# Mikrobus-Proto-18.net
KiCad netlist of a schematic drawn in EAGLE
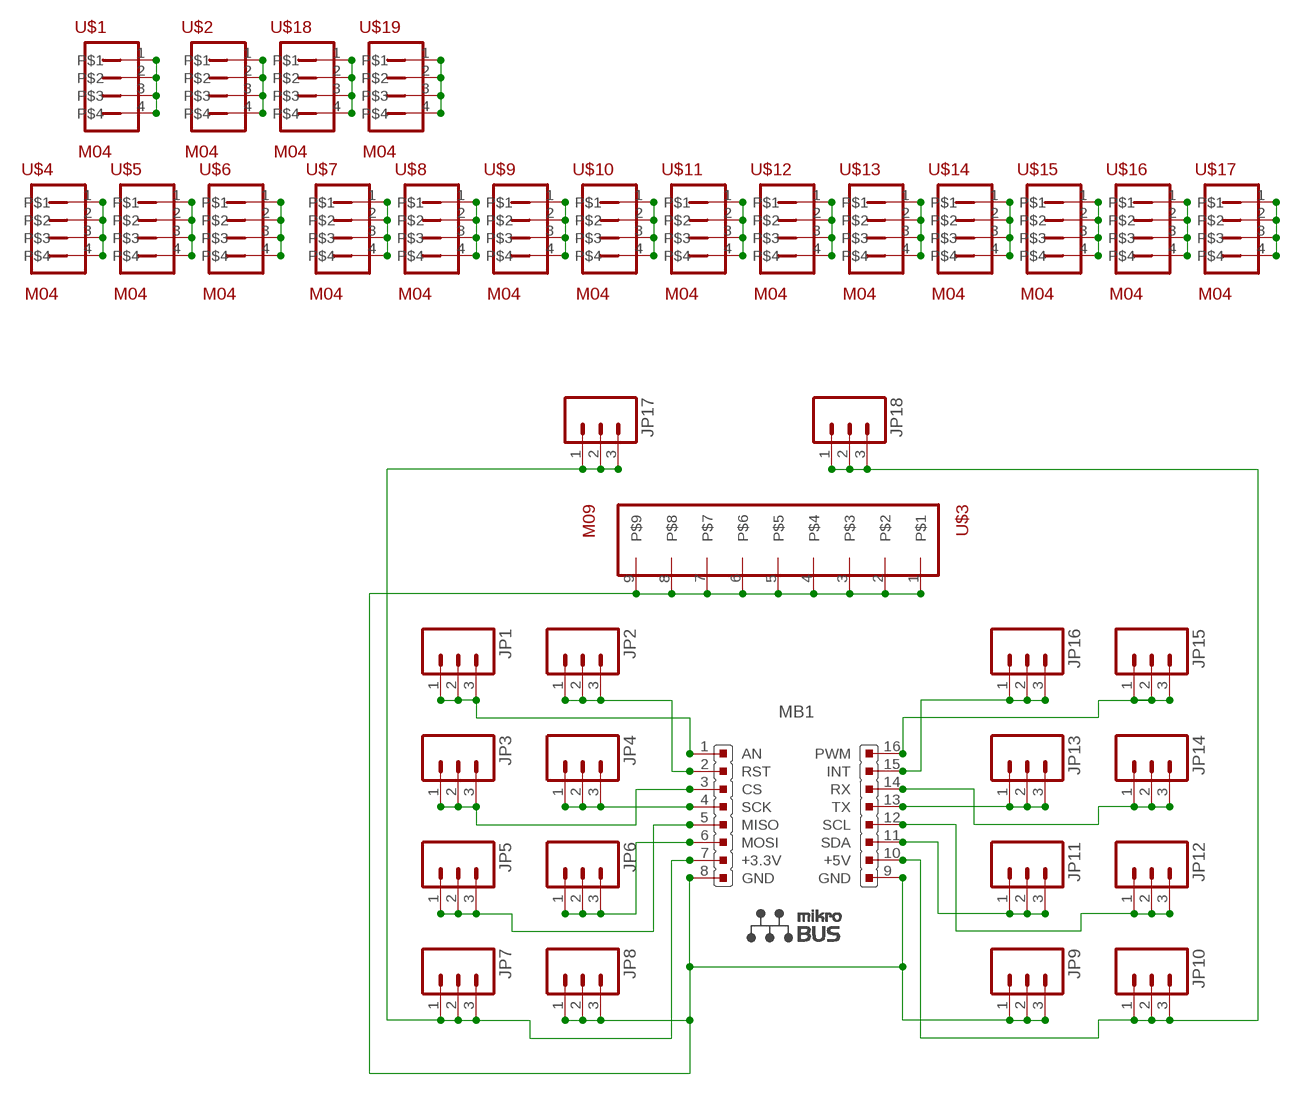
[diagram p0: schematic, sheet 1]

(export (version "E")
  (design (tool "Eeschema 10.0.6"))
  (components
    (comp (ref "JP1")
      (value "M03PTH")
      (footprint "eagle-import:1X03")
      (libsource (lib "eagle-import") (part "M03PTH"))
    )
    (comp (ref "JP2")
      (value "M03PTH")
      (footprint "eagle-import:1X03")
      (libsource (lib "eagle-import") (part "M03PTH"))
    )
    (comp (ref "JP3")
      (value "M03PTH")
      (footprint "eagle-import:1X03")
      (libsource (lib "eagle-import") (part "M03PTH"))
    )
    (comp (ref "JP4")
      (value "M03PTH")
      (footprint "eagle-import:1X03")
      (libsource (lib "eagle-import") (part "M03PTH"))
    )
    (comp (ref "JP5")
      (value "M03PTH")
      (footprint "eagle-import:1X03")
      (libsource (lib "eagle-import") (part "M03PTH"))
    )
    (comp (ref "JP6")
      (value "M03PTH")
      (footprint "eagle-import:1X03")
      (libsource (lib "eagle-import") (part "M03PTH"))
    )
    (comp (ref "JP7")
      (value "M03PTH")
      (footprint "eagle-import:1X03")
      (libsource (lib "eagle-import") (part "M03PTH"))
    )
    (comp (ref "JP8")
      (value "M03PTH")
      (footprint "eagle-import:1X03")
      (libsource (lib "eagle-import") (part "M03PTH"))
    )
    (comp (ref "JP9")
      (value "M03PTH")
      (footprint "eagle-import:1X03")
      (libsource (lib "eagle-import") (part "M03PTH"))
    )
    (comp (ref "JP10")
      (value "M03PTH")
      (footprint "eagle-import:1X03")
      (libsource (lib "eagle-import") (part "M03PTH"))
    )
    (comp (ref "JP11")
      (value "M03PTH")
      (footprint "eagle-import:1X03")
      (libsource (lib "eagle-import") (part "M03PTH"))
    )
    (comp (ref "JP12")
      (value "M03PTH")
      (footprint "eagle-import:1X03")
      (libsource (lib "eagle-import") (part "M03PTH"))
    )
    (comp (ref "JP13")
      (value "M03PTH")
      (footprint "eagle-import:1X03")
      (libsource (lib "eagle-import") (part "M03PTH"))
    )
    (comp (ref "JP14")
      (value "M03PTH")
      (footprint "eagle-import:1X03")
      (libsource (lib "eagle-import") (part "M03PTH"))
    )
    (comp (ref "JP15")
      (value "M03PTH")
      (footprint "eagle-import:1X03")
      (libsource (lib "eagle-import") (part "M03PTH"))
    )
    (comp (ref "JP16")
      (value "M03PTH")
      (footprint "eagle-import:1X03")
      (libsource (lib "eagle-import") (part "M03PTH"))
    )
    (comp (ref "JP17")
      (value "M03PTH")
      (footprint "eagle-import:1X03")
      (libsource (lib "eagle-import") (part "M03PTH"))
    )
    (comp (ref "JP18")
      (value "M03PTH")
      (footprint "eagle-import:1X03")
      (libsource (lib "eagle-import") (part "M03PTH"))
    )
    (comp (ref "MB1")
      (value "MIKROBUS")
      (footprint "eagle-import:MIKROBUS")
      (libsource (lib "eagle-import") (part "MIKROBUS"))
    )
    (comp (ref "U$1")
      (value "M04")
      (footprint "eagle-import:1X04")
      (libsource (lib "eagle-import") (part "M04"))
    )
    (comp (ref "U$2")
      (value "M04")
      (footprint "eagle-import:1X04")
      (libsource (lib "eagle-import") (part "M04"))
    )
    (comp (ref "U$3")
      (value "M09")
      (footprint "eagle-import:1X09")
      (libsource (lib "eagle-import") (part "M09"))
    )
    (comp (ref "U$4")
      (value "M04")
      (footprint "eagle-import:1X04")
      (libsource (lib "eagle-import") (part "M04"))
    )
    (comp (ref "U$5")
      (value "M04")
      (footprint "eagle-import:1X04")
      (libsource (lib "eagle-import") (part "M04"))
    )
    (comp (ref "U$6")
      (value "M04")
      (footprint "eagle-import:1X04")
      (libsource (lib "eagle-import") (part "M04"))
    )
    (comp (ref "U$7")
      (value "M04")
      (footprint "eagle-import:1X04")
      (libsource (lib "eagle-import") (part "M04"))
    )
    (comp (ref "U$8")
      (value "M04")
      (footprint "eagle-import:1X04")
      (libsource (lib "eagle-import") (part "M04"))
    )
    (comp (ref "U$9")
      (value "M04")
      (footprint "eagle-import:1X04")
      (libsource (lib "eagle-import") (part "M04"))
    )
    (comp (ref "U$10")
      (value "M04")
      (footprint "eagle-import:1X04")
      (libsource (lib "eagle-import") (part "M04"))
    )
    (comp (ref "U$11")
      (value "M04")
      (footprint "eagle-import:1X04")
      (libsource (lib "eagle-import") (part "M04"))
    )
    (comp (ref "U$12")
      (value "M04")
      (footprint "eagle-import:1X04")
      (libsource (lib "eagle-import") (part "M04"))
    )
    (comp (ref "U$13")
      (value "M04")
      (footprint "eagle-import:1X04")
      (libsource (lib "eagle-import") (part "M04"))
    )
    (comp (ref "U$14")
      (value "M04")
      (footprint "eagle-import:1X04")
      (libsource (lib "eagle-import") (part "M04"))
    )
    (comp (ref "U$15")
      (value "M04")
      (footprint "eagle-import:1X04")
      (libsource (lib "eagle-import") (part "M04"))
    )
    (comp (ref "U$16")
      (value "M04")
      (footprint "eagle-import:1X04")
      (libsource (lib "eagle-import") (part "M04"))
    )
    (comp (ref "U$17")
      (value "M04")
      (footprint "eagle-import:1X04")
      (libsource (lib "eagle-import") (part "M04"))
    )
    (comp (ref "U$18")
      (value "M04")
      (footprint "eagle-import:1X04")
      (libsource (lib "eagle-import") (part "M04"))
    )
    (comp (ref "U$19")
      (value "M04")
      (footprint "eagle-import:1X04")
      (libsource (lib "eagle-import") (part "M04"))
    )
  )
  (nets
    (net (code "1") (name "Net-(MB1-+3.3V)") (class "Default")
      (node (ref "JP17") (pin "1") (pinfunction "1_1") (pintype "passive"))
      (node (ref "JP17") (pin "2") (pinfunction "2_2") (pintype "passive"))
      (node (ref "JP17") (pin "3") (pinfunction "3_3") (pintype "passive"))
      (node (ref "JP7") (pin "1") (pinfunction "1_1") (pintype "passive"))
      (node (ref "JP7") (pin "2") (pinfunction "2_2") (pintype "passive"))
      (node (ref "JP7") (pin "3") (pinfunction "3_3") (pintype "passive"))
      (node (ref "MB1") (pin "7") (pinfunction "+3.3V_7") (pintype "passive"))
    )
    (net (code "2") (name "Net-(MB1-+5V)") (class "Default")
      (node (ref "JP10") (pin "1") (pinfunction "1_1") (pintype "passive"))
      (node (ref "JP10") (pin "2") (pinfunction "2_2") (pintype "passive"))
      (node (ref "JP10") (pin "3") (pinfunction "3_3") (pintype "passive"))
      (node (ref "JP18") (pin "1") (pinfunction "1_1") (pintype "passive"))
      (node (ref "JP18") (pin "2") (pinfunction "2_2") (pintype "passive"))
      (node (ref "JP18") (pin "3") (pinfunction "3_3") (pintype "passive"))
      (node (ref "MB1") (pin "10") (pinfunction "+5V_10") (pintype "passive"))
    )
    (net (code "3") (name "Net-(MB1-AN)") (class "Default")
      (node (ref "JP1") (pin "1") (pinfunction "1_1") (pintype "passive"))
      (node (ref "JP1") (pin "2") (pinfunction "2_2") (pintype "passive"))
      (node (ref "JP1") (pin "3") (pinfunction "3_3") (pintype "passive"))
      (node (ref "MB1") (pin "1") (pinfunction "AN_1") (pintype "bidirectional"))
    )
    (net (code "4") (name "Net-(MB1-CS)") (class "Default")
      (node (ref "JP3") (pin "1") (pinfunction "1_1") (pintype "passive"))
      (node (ref "JP3") (pin "2") (pinfunction "2_2") (pintype "passive"))
      (node (ref "JP3") (pin "3") (pinfunction "3_3") (pintype "passive"))
      (node (ref "MB1") (pin "3") (pinfunction "CS_3") (pintype "bidirectional"))
    )
    (net (code "5") (name "Net-(MB1-INT)") (class "Default")
      (node (ref "JP16") (pin "1") (pinfunction "1_1") (pintype "passive"))
      (node (ref "JP16") (pin "2") (pinfunction "2_2") (pintype "passive"))
      (node (ref "JP16") (pin "3") (pinfunction "3_3") (pintype "passive"))
      (node (ref "MB1") (pin "15") (pinfunction "INT_15") (pintype "bidirectional"))
    )
    (net (code "6") (name "Net-(MB1-MISO)") (class "Default")
      (node (ref "JP5") (pin "1") (pinfunction "1_1") (pintype "passive"))
      (node (ref "JP5") (pin "2") (pinfunction "2_2") (pintype "passive"))
      (node (ref "JP5") (pin "3") (pinfunction "3_3") (pintype "passive"))
      (node (ref "MB1") (pin "5") (pinfunction "MISO_5") (pintype "bidirectional"))
    )
    (net (code "7") (name "Net-(MB1-MOSI)") (class "Default")
      (node (ref "JP6") (pin "1") (pinfunction "1_1") (pintype "passive"))
      (node (ref "JP6") (pin "2") (pinfunction "2_2") (pintype "passive"))
      (node (ref "JP6") (pin "3") (pinfunction "3_3") (pintype "passive"))
      (node (ref "MB1") (pin "6") (pinfunction "MOSI_6") (pintype "bidirectional"))
    )
    (net (code "8") (name "Net-(MB1-PWM)") (class "Default")
      (node (ref "JP15") (pin "1") (pinfunction "1_1") (pintype "passive"))
      (node (ref "JP15") (pin "2") (pinfunction "2_2") (pintype "passive"))
      (node (ref "JP15") (pin "3") (pinfunction "3_3") (pintype "passive"))
      (node (ref "MB1") (pin "16") (pinfunction "PWM_16") (pintype "bidirectional"))
    )
    (net (code "9") (name "Net-(MB1-RST)") (class "Default")
      (node (ref "JP2") (pin "1") (pinfunction "1_1") (pintype "passive"))
      (node (ref "JP2") (pin "2") (pinfunction "2_2") (pintype "passive"))
      (node (ref "JP2") (pin "3") (pinfunction "3_3") (pintype "passive"))
      (node (ref "MB1") (pin "2") (pinfunction "RST_2") (pintype "bidirectional"))
    )
    (net (code "10") (name "Net-(MB1-RX)") (class "Default")
      (node (ref "JP14") (pin "1") (pinfunction "1_1") (pintype "passive"))
      (node (ref "JP14") (pin "2") (pinfunction "2_2") (pintype "passive"))
      (node (ref "JP14") (pin "3") (pinfunction "3_3") (pintype "passive"))
      (node (ref "MB1") (pin "14") (pinfunction "RX_14") (pintype "bidirectional"))
    )
    (net (code "11") (name "Net-(MB1-SCK)") (class "Default")
      (node (ref "JP4") (pin "1") (pinfunction "1_1") (pintype "passive"))
      (node (ref "JP4") (pin "2") (pinfunction "2_2") (pintype "passive"))
      (node (ref "JP4") (pin "3") (pinfunction "3_3") (pintype "passive"))
      (node (ref "MB1") (pin "4") (pinfunction "SCK_4") (pintype "bidirectional"))
    )
    (net (code "12") (name "Net-(MB1-SCL)") (class "Default")
      (node (ref "JP12") (pin "1") (pinfunction "1_1") (pintype "passive"))
      (node (ref "JP12") (pin "2") (pinfunction "2_2") (pintype "passive"))
      (node (ref "JP12") (pin "3") (pinfunction "3_3") (pintype "passive"))
      (node (ref "MB1") (pin "12") (pinfunction "SCL_12") (pintype "bidirectional"))
    )
    (net (code "13") (name "Net-(MB1-SDA)") (class "Default")
      (node (ref "JP11") (pin "1") (pinfunction "1_1") (pintype "passive"))
      (node (ref "JP11") (pin "2") (pinfunction "2_2") (pintype "passive"))
      (node (ref "JP11") (pin "3") (pinfunction "3_3") (pintype "passive"))
      (node (ref "MB1") (pin "11") (pinfunction "SDA_11") (pintype "bidirectional"))
    )
    (net (code "14") (name "Net-(MB1-TX)") (class "Default")
      (node (ref "JP13") (pin "1") (pinfunction "1_1") (pintype "passive"))
      (node (ref "JP13") (pin "2") (pinfunction "2_2") (pintype "passive"))
      (node (ref "JP13") (pin "3") (pinfunction "3_3") (pintype "passive"))
      (node (ref "MB1") (pin "13") (pinfunction "TX_13") (pintype "bidirectional"))
    )
    (net (code "15") (name "Net-(U$1-P$1)") (class "Default")
      (node (ref "U$1") (pin "1") (pinfunction "P$1_1") (pintype "passive"))
      (node (ref "U$1") (pin "2") (pinfunction "P$2_2") (pintype "passive"))
      (node (ref "U$1") (pin "3") (pinfunction "P$3_3") (pintype "passive"))
      (node (ref "U$1") (pin "4") (pinfunction "P$4_4") (pintype "passive"))
    )
    (net (code "16") (name "Net-(U$2-P$1)") (class "Default")
      (node (ref "U$2") (pin "1") (pinfunction "P$1_1") (pintype "passive"))
      (node (ref "U$2") (pin "2") (pinfunction "P$2_2") (pintype "passive"))
      (node (ref "U$2") (pin "3") (pinfunction "P$3_3") (pintype "passive"))
      (node (ref "U$2") (pin "4") (pinfunction "P$4_4") (pintype "passive"))
    )
    (net (code "17") (name "Net-(U$3-P$1)") (class "Default")
      (node (ref "JP8") (pin "1") (pinfunction "1_1") (pintype "passive"))
      (node (ref "JP8") (pin "2") (pinfunction "2_2") (pintype "passive"))
      (node (ref "JP8") (pin "3") (pinfunction "3_3") (pintype "passive"))
      (node (ref "JP9") (pin "1") (pinfunction "1_1") (pintype "passive"))
      (node (ref "JP9") (pin "2") (pinfunction "2_2") (pintype "passive"))
      (node (ref "JP9") (pin "3") (pinfunction "3_3") (pintype "passive"))
      (node (ref "MB1") (pin "8") (pinfunction "GND_8") (pintype "passive"))
      (node (ref "MB1") (pin "9") (pinfunction "GND_9") (pintype "passive"))
      (node (ref "U$3") (pin "1") (pinfunction "P$1_1") (pintype "bidirectional"))
      (node (ref "U$3") (pin "2") (pinfunction "P$2_2") (pintype "bidirectional"))
      (node (ref "U$3") (pin "3") (pinfunction "P$3_3") (pintype "bidirectional"))
      (node (ref "U$3") (pin "4") (pinfunction "P$4_4") (pintype "bidirectional"))
      (node (ref "U$3") (pin "5") (pinfunction "P$5_5") (pintype "bidirectional"))
      (node (ref "U$3") (pin "6") (pinfunction "P$6_6") (pintype "bidirectional"))
      (node (ref "U$3") (pin "7") (pinfunction "P$7_7") (pintype "bidirectional"))
      (node (ref "U$3") (pin "8") (pinfunction "P$8_8") (pintype "bidirectional"))
      (node (ref "U$3") (pin "9") (pinfunction "P$9_9") (pintype "bidirectional"))
    )
    (net (code "18") (name "Net-(U$4-P$1)") (class "Default")
      (node (ref "U$4") (pin "1") (pinfunction "P$1_1") (pintype "passive"))
      (node (ref "U$4") (pin "2") (pinfunction "P$2_2") (pintype "passive"))
      (node (ref "U$4") (pin "3") (pinfunction "P$3_3") (pintype "passive"))
      (node (ref "U$4") (pin "4") (pinfunction "P$4_4") (pintype "passive"))
    )
    (net (code "19") (name "Net-(U$5-P$1)") (class "Default")
      (node (ref "U$5") (pin "1") (pinfunction "P$1_1") (pintype "passive"))
      (node (ref "U$5") (pin "2") (pinfunction "P$2_2") (pintype "passive"))
      (node (ref "U$5") (pin "3") (pinfunction "P$3_3") (pintype "passive"))
      (node (ref "U$5") (pin "4") (pinfunction "P$4_4") (pintype "passive"))
    )
    (net (code "20") (name "Net-(U$6-P$1)") (class "Default")
      (node (ref "U$6") (pin "1") (pinfunction "P$1_1") (pintype "passive"))
      (node (ref "U$6") (pin "2") (pinfunction "P$2_2") (pintype "passive"))
      (node (ref "U$6") (pin "3") (pinfunction "P$3_3") (pintype "passive"))
      (node (ref "U$6") (pin "4") (pinfunction "P$4_4") (pintype "passive"))
    )
    (net (code "21") (name "Net-(U$7-P$1)") (class "Default")
      (node (ref "U$7") (pin "1") (pinfunction "P$1_1") (pintype "passive"))
      (node (ref "U$7") (pin "2") (pinfunction "P$2_2") (pintype "passive"))
      (node (ref "U$7") (pin "3") (pinfunction "P$3_3") (pintype "passive"))
      (node (ref "U$7") (pin "4") (pinfunction "P$4_4") (pintype "passive"))
    )
    (net (code "22") (name "Net-(U$8-P$1)") (class "Default")
      (node (ref "U$8") (pin "1") (pinfunction "P$1_1") (pintype "passive"))
      (node (ref "U$8") (pin "2") (pinfunction "P$2_2") (pintype "passive"))
      (node (ref "U$8") (pin "3") (pinfunction "P$3_3") (pintype "passive"))
      (node (ref "U$8") (pin "4") (pinfunction "P$4_4") (pintype "passive"))
    )
    (net (code "23") (name "Net-(U$9-P$1)") (class "Default")
      (node (ref "U$9") (pin "1") (pinfunction "P$1_1") (pintype "passive"))
      (node (ref "U$9") (pin "2") (pinfunction "P$2_2") (pintype "passive"))
      (node (ref "U$9") (pin "3") (pinfunction "P$3_3") (pintype "passive"))
      (node (ref "U$9") (pin "4") (pinfunction "P$4_4") (pintype "passive"))
    )
    (net (code "24") (name "Net-(U$10-P$1)") (class "Default")
      (node (ref "U$10") (pin "1") (pinfunction "P$1_1") (pintype "passive"))
      (node (ref "U$10") (pin "2") (pinfunction "P$2_2") (pintype "passive"))
      (node (ref "U$10") (pin "3") (pinfunction "P$3_3") (pintype "passive"))
      (node (ref "U$10") (pin "4") (pinfunction "P$4_4") (pintype "passive"))
    )
    (net (code "25") (name "Net-(U$11-P$1)") (class "Default")
      (node (ref "U$11") (pin "1") (pinfunction "P$1_1") (pintype "passive"))
      (node (ref "U$11") (pin "2") (pinfunction "P$2_2") (pintype "passive"))
      (node (ref "U$11") (pin "3") (pinfunction "P$3_3") (pintype "passive"))
      (node (ref "U$11") (pin "4") (pinfunction "P$4_4") (pintype "passive"))
    )
    (net (code "26") (name "Net-(U$12-P$1)") (class "Default")
      (node (ref "U$12") (pin "1") (pinfunction "P$1_1") (pintype "passive"))
      (node (ref "U$12") (pin "2") (pinfunction "P$2_2") (pintype "passive"))
      (node (ref "U$12") (pin "3") (pinfunction "P$3_3") (pintype "passive"))
      (node (ref "U$12") (pin "4") (pinfunction "P$4_4") (pintype "passive"))
    )
    (net (code "27") (name "Net-(U$13-P$1)") (class "Default")
      (node (ref "U$13") (pin "1") (pinfunction "P$1_1") (pintype "passive"))
      (node (ref "U$13") (pin "2") (pinfunction "P$2_2") (pintype "passive"))
      (node (ref "U$13") (pin "3") (pinfunction "P$3_3") (pintype "passive"))
      (node (ref "U$13") (pin "4") (pinfunction "P$4_4") (pintype "passive"))
    )
    (net (code "28") (name "Net-(U$14-P$1)") (class "Default")
      (node (ref "U$14") (pin "1") (pinfunction "P$1_1") (pintype "passive"))
      (node (ref "U$14") (pin "2") (pinfunction "P$2_2") (pintype "passive"))
      (node (ref "U$14") (pin "3") (pinfunction "P$3_3") (pintype "passive"))
      (node (ref "U$14") (pin "4") (pinfunction "P$4_4") (pintype "passive"))
    )
    (net (code "29") (name "Net-(U$15-P$1)") (class "Default")
      (node (ref "U$15") (pin "1") (pinfunction "P$1_1") (pintype "passive"))
      (node (ref "U$15") (pin "2") (pinfunction "P$2_2") (pintype "passive"))
      (node (ref "U$15") (pin "3") (pinfunction "P$3_3") (pintype "passive"))
      (node (ref "U$15") (pin "4") (pinfunction "P$4_4") (pintype "passive"))
    )
    (net (code "30") (name "Net-(U$16-P$1)") (class "Default")
      (node (ref "U$16") (pin "1") (pinfunction "P$1_1") (pintype "passive"))
      (node (ref "U$16") (pin "2") (pinfunction "P$2_2") (pintype "passive"))
      (node (ref "U$16") (pin "3") (pinfunction "P$3_3") (pintype "passive"))
      (node (ref "U$16") (pin "4") (pinfunction "P$4_4") (pintype "passive"))
    )
    (net (code "31") (name "Net-(U$17-P$1)") (class "Default")
      (node (ref "U$17") (pin "1") (pinfunction "P$1_1") (pintype "passive"))
      (node (ref "U$17") (pin "2") (pinfunction "P$2_2") (pintype "passive"))
      (node (ref "U$17") (pin "3") (pinfunction "P$3_3") (pintype "passive"))
      (node (ref "U$17") (pin "4") (pinfunction "P$4_4") (pintype "passive"))
    )
    (net (code "32") (name "Net-(U$18-P$1)") (class "Default")
      (node (ref "U$18") (pin "1") (pinfunction "P$1_1") (pintype "passive"))
      (node (ref "U$18") (pin "2") (pinfunction "P$2_2") (pintype "passive"))
      (node (ref "U$18") (pin "3") (pinfunction "P$3_3") (pintype "passive"))
      (node (ref "U$18") (pin "4") (pinfunction "P$4_4") (pintype "passive"))
    )
    (net (code "33") (name "Net-(U$19-P$1)") (class "Default")
      (node (ref "U$19") (pin "1") (pinfunction "P$1_1") (pintype "passive"))
      (node (ref "U$19") (pin "2") (pinfunction "P$2_2") (pintype "passive"))
      (node (ref "U$19") (pin "3") (pinfunction "P$3_3") (pintype "passive"))
      (node (ref "U$19") (pin "4") (pinfunction "P$4_4") (pintype "passive"))
    )
  )
)
